# Power_Supply.net
KiCad netlist of a schematic drawn in Altium Designer
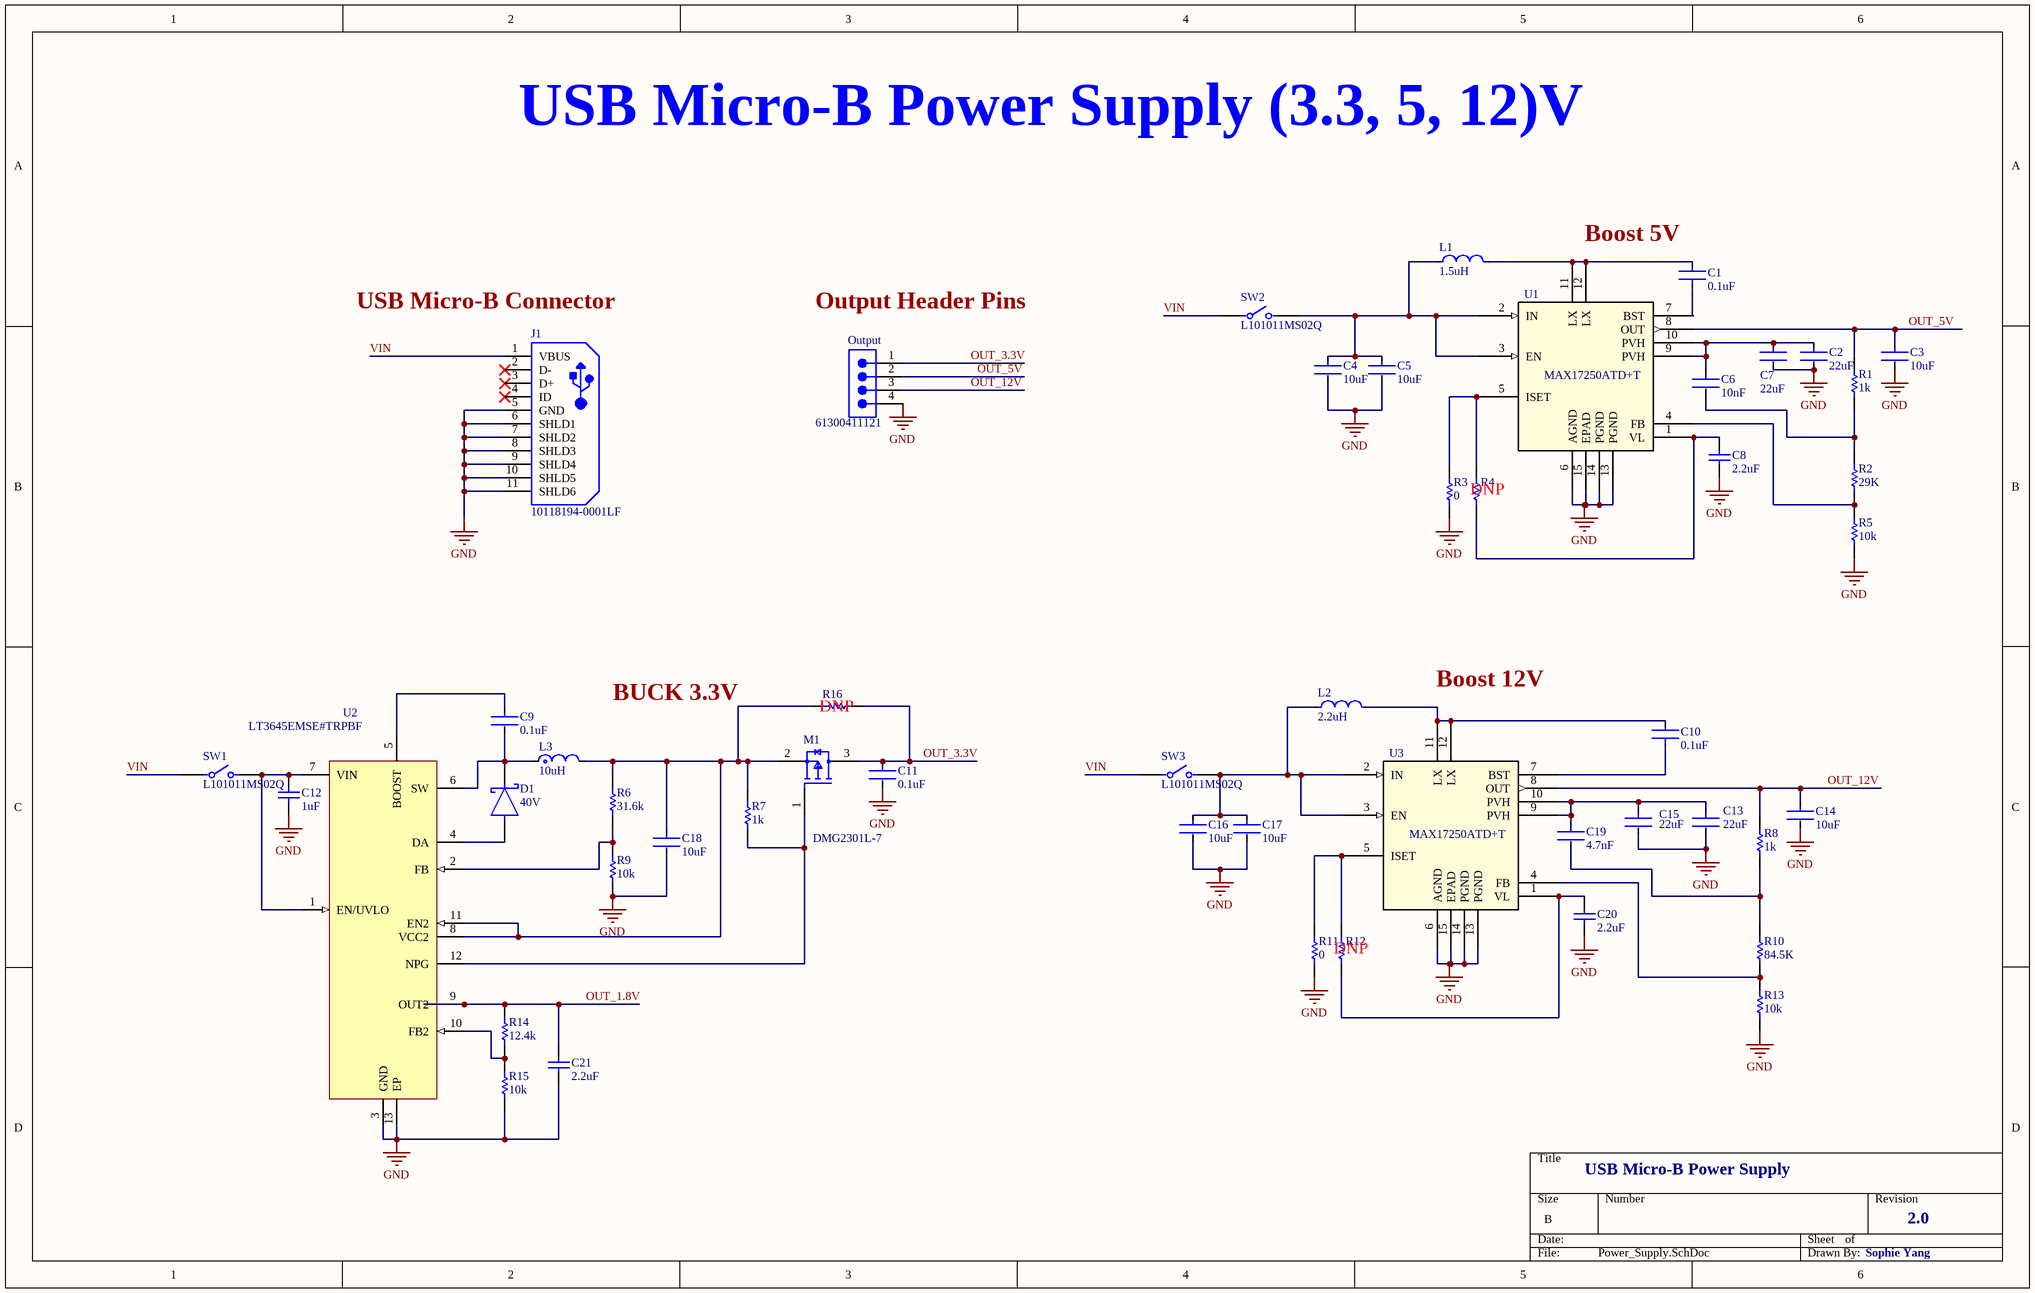
[diagram p0: Power_Supply.SchDoc]

(export (version "E")
  (design (tool "Eeschema 10.0.6"))
  (components
    (comp (ref "C1")
      (value "0.1uF")
      (footprint "CC0805KRX7R9BB104")
      (fields
        (field (name "MANUFACTURER") "Yageo")
        (field (name "MANUFACTURER PART NUMBER") "CC0805KRX7R9BB104")
        (field (name "LCSC PART NUMBER") "C49678")
      )
      (libsource (lib "Schlib") (part "CC0805KRX7R9BB104"))
    )
    (comp (ref "C2")
      (value "22uF")
      (footprint "GRM21BR61C226ME44L")
      (description "CAP CER 22UF 16V X5R 0805")
      (fields
        (field (name "MANUFACTURER") "Murata")
        (field (name "MANUFACTURER PART NUMBER") "GRM21BR61C226ME44L")
      )
      (libsource (lib "Schlib") (part "GRM21BR61C226ME44L"))
    )
    (comp (ref "C3")
      (value "10uF")
      (footprint "GRM21BR61C106KE15K")
      (fields
        (field (name "MANUFACTURER") "Murata")
        (field (name "MANUFACTURER PART NUMBER") "GRM21BR61C106KE15K")
        (field (name "LCSC PART NUMBER") "C408141")
      )
      (libsource (lib "Schlib") (part "GRM21BR61C106KE15K"))
    )
    (comp (ref "C4")
      (value "10uF")
      (footprint "GRM21BR61C106KE15K")
      (fields
        (field (name "MANUFACTURER") "Murata")
        (field (name "MANUFACTURER PART NUMBER") "GRM21BR61C106KE15K")
        (field (name "LCSC PART NUMBER") "C408141")
      )
      (libsource (lib "Schlib") (part "GRM21BR61C106KE15K"))
    )
    (comp (ref "C5")
      (value "10uF")
      (footprint "GRM21BR61C106KE15K")
      (fields
        (field (name "MANUFACTURER") "Murata")
        (field (name "MANUFACTURER PART NUMBER") "GRM21BR61C106KE15K")
        (field (name "LCSC PART NUMBER") "C408141")
      )
      (libsource (lib "Schlib") (part "GRM21BR61C106KE15K"))
    )
    (comp (ref "C6")
      (value "10nF")
      (footprint "C0805C103K5RACTU")
      (fields
        (field (name "MANUFACTURER") "KEMET")
        (field (name "MANUFACTURER PART NUMBER") "C0805C103K5RAC-TU")
      )
      (libsource (lib "Schlib") (part "C0805C103K5RAC-TU"))
    )
    (comp (ref "C7")
      (value "22uF")
      (footprint "GRM21BR61C226ME44L")
      (description "CAP CER 22UF 16V X5R 0805")
      (fields
        (field (name "MANUFACTURER") "Murata")
        (field (name "MANUFACTURER PART NUMBER") "GRM21BR61C226ME44L")
      )
      (libsource (lib "Schlib") (part "GRM21BR61C226ME44L"))
    )
    (comp (ref "C8")
      (value "2.2uF")
      (footprint "C0805C225M8RACTU")
      (description "CAP CER 2.2UF 10V X7R 0805")
      (fields
        (field (name "MANUFACTURER") "KEMET")
        (field (name "MANUFACTURER PART NUMBER") "C0805C225M8RACTU")
      )
      (libsource (lib "Schlib") (part "C0805C225M8RACTU"))
    )
    (comp (ref "C9")
      (value "0.1uF")
      (footprint "CC0805KRX7R9BB104")
      (fields
        (field (name "MANUFACTURER") "Yageo")
        (field (name "MANUFACTURER PART NUMBER") "CC0805KRX7R9BB104")
        (field (name "LCSC PART NUMBER") "C49678")
      )
      (libsource (lib "Schlib") (part "CC0805KRX7R9BB104"))
    )
    (comp (ref "C10")
      (value "0.1uF")
      (footprint "CC0805KRX7R9BB104")
      (fields
        (field (name "MANUFACTURER") "Yageo")
        (field (name "MANUFACTURER PART NUMBER") "CC0805KRX7R9BB104")
        (field (name "LCSC PART NUMBER") "C49678")
      )
      (libsource (lib "Schlib") (part "CC0805KRX7R9BB104"))
    )
    (comp (ref "C11")
      (value "0.1uF")
      (footprint "CC0805KRX7R9BB104")
      (fields
        (field (name "MANUFACTURER") "Yageo")
        (field (name "MANUFACTURER PART NUMBER") "CC0805KRX7R9BB104")
        (field (name "LCSC PART NUMBER") "C49678")
      )
      (libsource (lib "Schlib") (part "CC0805KRX7R9BB104"))
    )
    (comp (ref "C12")
      (value "1uF")
      (footprint "C0805C105K4RACTU")
      (description "CAP CER 1UF 16V X7R 0805")
      (fields
        (field (name "MANUFACTURER") "KEMET")
        (field (name "MANUFACTURER PART NUMBER") "C0805C105K4RACTU")
      )
      (libsource (lib "Schlib") (part "C0805C105K4RACTU"))
    )
    (comp (ref "C13")
      (value "22uF")
      (footprint "GRM32ER71E226KE15L")
      (description "CAP CER 22UF 25V X7R 1210")
      (fields
        (field (name "MANUFACTURER") "Murata")
        (field (name "MANUFACTURER PART NUMBER") "GRM32ER71E226KE15L")
      )
      (libsource (lib "Schlib") (part "GRM32ER71E226KE15L"))
    )
    (comp (ref "C14")
      (value "10uF")
      (footprint "GRM21BZ71E106KE15L")
      (description "CAP CER 10UF 25V X7R 0805")
      (fields
        (field (name "MANUFACTURER") "Murata")
        (field (name "MANUFACTURER PART NUMBER") "GRM21BZ71E106KE15L")
      )
      (libsource (lib "Schlib") (part "GRM21BZ71E106KE15L"))
    )
    (comp (ref "C15")
      (value "22uF")
      (footprint "GRM32ER71E226KE15L")
      (description "CAP CER 22UF 25V X7R 1210")
      (fields
        (field (name "MANUFACTURER") "Murata")
        (field (name "MANUFACTURER PART NUMBER") "GRM32ER71E226KE15L")
      )
      (libsource (lib "Schlib") (part "GRM32ER71E226KE15L"))
    )
    (comp (ref "C16")
      (value "10uF")
      (footprint "GRM21BR61C106KE15K")
      (fields
        (field (name "MANUFACTURER") "Murata")
        (field (name "MANUFACTURER PART NUMBER") "GRM21BR61C106KE15K")
        (field (name "LCSC PART NUMBER") "C408141")
      )
      (libsource (lib "Schlib") (part "GRM21BR61C106KE15K"))
    )
    (comp (ref "C17")
      (value "10uF")
      (footprint "GRM21BR61C106KE15K")
      (fields
        (field (name "MANUFACTURER") "Murata")
        (field (name "MANUFACTURER PART NUMBER") "GRM21BR61C106KE15K")
        (field (name "LCSC PART NUMBER") "C408141")
      )
      (libsource (lib "Schlib") (part "GRM21BR61C106KE15K"))
    )
    (comp (ref "C18")
      (value "10uF")
      (footprint "GRM21BR61C106KE15K")
      (fields
        (field (name "MANUFACTURER") "Murata")
        (field (name "MANUFACTURER PART NUMBER") "GRM21BR61C106KE15K")
        (field (name "LCSC PART NUMBER") "C408141")
      )
      (libsource (lib "Schlib") (part "GRM21BR61C106KE15K"))
    )
    (comp (ref "C19")
      (value "4.7nF")
      (footprint "CC0805KRX7R9BB472")
      (fields
        (field (name "MANUFACTURER") "Yageo")
        (field (name "MANUFACTURER PART NUMBER") "CC0805KRX7R9BB472")
        (field (name "LCSC PART NUMBER") "C107153")
      )
      (libsource (lib "Schlib") (part "CC0805KRX7R9BB472"))
    )
    (comp (ref "C20")
      (value "2.2uF")
      (footprint "C0805C225M8RACTU")
      (description "CAP CER 2.2UF 10V X7R 0805")
      (fields
        (field (name "MANUFACTURER") "KEMET")
        (field (name "MANUFACTURER PART NUMBER") "C0805C225M8RACTU")
      )
      (libsource (lib "Schlib") (part "C0805C225M8RACTU"))
    )
    (comp (ref "C21")
      (value "2.2uF")
      (footprint "C0805C225M8RACTU")
      (description "CAP CER 2.2UF 10V X7R 0805")
      (fields
        (field (name "MANUFACTURER") "KEMET")
        (field (name "MANUFACTURER PART NUMBER") "C0805C225M8RACTU")
      )
      (libsource (lib "Schlib") (part "C0805C225M8RACTU"))
    )
    (comp (ref "D1")
      (value "40V")
      (footprint "B5819WS-TP")
      (description "Rectifier Diode, Schottky, 1 Phase, 1 Element, 1A, 40V V(RRM), Silicon")
      (fields (field (name "MANUFACTURER") "MCC") (field (name "MANUFACTURER PART NUMBER") "B5819WS-TP"))
      (libsource (lib "Schlib") (part "B5819WS-TP"))
    )
    (comp (ref "J1")
      (value "10118194-0001LF")
      (footprint "10118194-0001LF")
      (description "CONN RCPT USB2.0 MICRO B SMD R/A")
      (fields (field (name "MANUFACTURER") "Amphenol ICC / FCI"))
      (libsource (lib "Schlib") (part "10118194-0001LF"))
    )
    (comp (ref "L1")
      (value "1.5uH")
      (footprint "IHLP2020CZER1R5M11")
      (description "FIXED IND 1.5UH 7.5A 18.5MOHM SM")
      (fields
        (field (name "MANUFACTURER") "Vishay Dale")
        (field (name "MANUFACTURER PART NUMBER") "IHLP2020CZER1R5M11")
      )
      (libsource (lib "Schlib") (part "IHLP2020CZER1R5M11"))
    )
    (comp (ref "L2")
      (value "2.2uH")
      (footprint "IHLP2020CZER2R2M11")
      (description "FIXED IND 2.2UH 6.75A 25MOHM SMD")
      (fields
        (field (name "MANUFACTURER") "Vishay Dale")
        (field (name "MANUFACTURER PART NUMBER") "IHLP2020CZER2R2M11")
      )
      (libsource (lib "Schlib") (part "IHLP2020CZER2R2M11"))
    )
    (comp (ref "L3")
      (value "10uH")
      (footprint "VLS6045EX-100M")
      (description "FIXED IND 10UH 3.4A 61 MOHM SMD")
      (fields (field (name "MANUFACTURER") "TDK") (field (name "MANUFACTURER PART NUMBER") "VLS6045EX-100M"))
      (libsource (lib "Schlib") (part "VLS6045EX-100M"))
    )
    (comp (ref "M1")
      (value "DMG2301L-7")
      (footprint "DMG2301L-7")
      (description "MOSFET P-CH 20V 3A SOT23")
      (fields (field (name "MANUFACTURER") "Diodes"))
      (libsource (lib "Schlib") (part "DMG2301L-7"))
    )
    (comp (ref "Output")
      (value "61300411121")
      (footprint "61300411121")
      (description "CONN HEADER VERT 4POS 2.54MM")
      (fields (field (name "MANUFACTURER") "Wurth Electronics"))
      (libsource (lib "Schlib") (part "61300411121"))
    )
    (comp (ref "R1")
      (value "1k")
      (footprint "RC0805FR-071KL")
      (description "RES 1K OHM 1% 1/8W 0805")
      (fields
        (field (name "MANUFACTURER") "Yageo")
        (field (name "MANUFACTURER PART NUMBER") "RC0805FR-071KL")
      )
      (libsource (lib "Schlib") (part "RC0805FR-071KL"))
    )
    (comp (ref "R2")
      (value "29K")
      (footprint "CRCW080528K7FKEA")
      (description "RES SMD 28.7K OHM 1% 1/8W 0805")
      (fields
        (field (name "MANUFACTURER") "Vishay")
        (field (name "MANUFACTURER PART NUMBER") "CRCW080528K7FKEA")
      )
      (libsource (lib "Schlib") (part "CRCW080528K7FKEA"))
    )
    (comp (ref "R3")
      (value "0")
      (footprint "CRCW08050000Z0EA")
      (description "RES SMD 0 OHM JUMPER 1/8W 0805")
      (fields
        (field (name "MANUFACTURER") "Vishay")
        (field (name "MANUFACTURER PART NUMBER") "CRCW08050000Z0EA")
      )
      (libsource (lib "Schlib") (part "CRCW08050000Z0EA"))
    )
    (comp (ref "R4")
      (value "DNP")
      (footprint "CRCW08050000Z0EA")
      (description "RES SMD 0 OHM JUMPER 1/8W 0805")
      (fields
        (field (name "MANUFACTURER") "Vishay")
        (field (name "MANUFACTURER PART NUMBER") "CRCW08050000Z0EA")
      )
      (libsource (lib "Schlib") (part "CRCW08050000Z0EA"))
    )
    (comp (ref "R5")
      (value "10k")
      (footprint "CRCW080510K0FKEA")
      (description "RES SMD 10K OHM 1% 1/8W 0805")
      (fields
        (field (name "MANUFACTURER") "Vishay")
        (field (name "MANUFACTURER PART NUMBER") "CRCW080510K0FKEA")
      )
      (libsource (lib "Schlib") (part "CRCW080510K0FKEA"))
    )
    (comp (ref "R6")
      (value "31.6k")
      (footprint "RC0805FR-0731K6L")
      (description "RES 31.6K OHM 1% 1/8W 0805")
      (fields
        (field (name "MANUFACTURER") "Yageo")
        (field (name "MANUFACTURER PART NUMBER") "RC0805FR-0731K6L")
      )
      (libsource (lib "Schlib") (part "RC0805FR-0731K6L"))
    )
    (comp (ref "R7")
      (value "1k")
      (footprint "RC0805FR-071KL")
      (description "RES 1K OHM 1% 1/8W 0805")
      (fields
        (field (name "MANUFACTURER") "Yageo")
        (field (name "MANUFACTURER PART NUMBER") "RC0805FR-071KL")
      )
      (libsource (lib "Schlib") (part "RC0805FR-071KL"))
    )
    (comp (ref "R8")
      (value "1k")
      (footprint "RC0805FR-071KL")
      (description "RES 1K OHM 1% 1/8W 0805")
      (fields
        (field (name "MANUFACTURER") "Yageo")
        (field (name "MANUFACTURER PART NUMBER") "RC0805FR-071KL")
      )
      (libsource (lib "Schlib") (part "RC0805FR-071KL"))
    )
    (comp (ref "R9")
      (value "10k")
      (footprint "CRCW080510K0FKEA")
      (description "RES SMD 10K OHM 1% 1/8W 0805")
      (fields
        (field (name "MANUFACTURER") "Vishay")
        (field (name "MANUFACTURER PART NUMBER") "CRCW080510K0FKEA")
      )
      (libsource (lib "Schlib") (part "CRCW080510K0FKEA"))
    )
    (comp (ref "R10")
      (value "84.5K")
      (footprint "CRCW080584K5FKEA")
      (description "RES SMD 84.5K OHM 1% 1/8W 0805")
      (fields
        (field (name "MANUFACTURER") "Vishay")
        (field (name "MANUFACTURER PART NUMBER") "CRCW080584K5FKEA")
      )
      (libsource (lib "Schlib") (part "CRCW080584K5FKEA"))
    )
    (comp (ref "R11")
      (value "0")
      (footprint "CRCW08050000Z0EA")
      (description "RES SMD 0 OHM JUMPER 1/8W 0805")
      (fields
        (field (name "MANUFACTURER") "Vishay")
        (field (name "MANUFACTURER PART NUMBER") "CRCW08050000Z0EA")
      )
      (libsource (lib "Schlib") (part "CRCW08050000Z0EA"))
    )
    (comp (ref "R12")
      (value "DNP")
      (footprint "CRCW08050000Z0EA")
      (description "RES SMD 0 OHM JUMPER 1/8W 0805")
      (fields
        (field (name "MANUFACTURER") "Vishay")
        (field (name "MANUFACTURER PART NUMBER") "CRCW08050000Z0EA")
      )
      (libsource (lib "Schlib") (part "CRCW08050000Z0EA"))
    )
    (comp (ref "R13")
      (value "10k")
      (footprint "CRCW080510K0FKEA")
      (description "RES SMD 10K OHM 1% 1/8W 0805")
      (fields
        (field (name "MANUFACTURER") "Vishay")
        (field (name "MANUFACTURER PART NUMBER") "CRCW080510K0FKEA")
      )
      (libsource (lib "Schlib") (part "CRCW080510K0FKEA"))
    )
    (comp (ref "R14")
      (value "12.4k")
      (footprint "CRCW080512K4FKEA")
      (description "RES SMD 12.4K OHM 1% 1/8W 0805")
      (fields
        (field (name "MANUFACTURER") "Vishay")
        (field (name "MANUFACTURER PART NUMBER") "CRCW080512K4FKEA")
      )
      (libsource (lib "Schlib") (part "CRCW080512K4FKEA"))
    )
    (comp (ref "R15")
      (value "10k")
      (footprint "CRCW080510K0FKEA")
      (description "RES SMD 10K OHM 1% 1/8W 0805")
      (fields
        (field (name "MANUFACTURER") "Vishay")
        (field (name "MANUFACTURER PART NUMBER") "CRCW080510K0FKEA")
      )
      (libsource (lib "Schlib") (part "CRCW080510K0FKEA"))
    )
    (comp (ref "R16")
      (value "DNP")
      (footprint "CRCW08050000Z0EA")
      (description "RES SMD 0 OHM JUMPER 1/8W 0805")
      (fields
        (field (name "MANUFACTURER") "Vishay")
        (field (name "MANUFACTURER PART NUMBER") "CRCW08050000Z0EA")
      )
      (libsource (lib "Schlib") (part "CRCW08050000Z0EA"))
    )
    (comp (ref "SW1")
      (value "L101011MS02Q")
      (footprint "FP-L101011MS02Q-MFG")
      (description "SWITCH SLIDE SPST 4A 125V")
      (libsource (lib "Schlib") (part "CMP-10038-000020-1"))
    )
    (comp (ref "SW2")
      (value "L101011MS02Q")
      (footprint "FP-L101011MS02Q-MFG")
      (description "SWITCH SLIDE SPST 4A 125V")
      (libsource (lib "Schlib") (part "CMP-10038-000020-1"))
    )
    (comp (ref "SW3")
      (value "L101011MS02Q")
      (footprint "FP-L101011MS02Q-MFG")
      (description "SWITCH SLIDE SPST 4A 125V")
      (libsource (lib "Schlib") (part "CMP-10038-000020-1"))
    )
    (comp (ref "U1")
      (value "MAX17250ATD+T")
      (footprint "MAX17250ATD+T")
      (description "IC REG BOOST ADJ 14TDFN")
      (fields (field (name "MANUFACTURER") "Maxim") (field (name "LCSC PART NUMBER") "C2072526"))
      (libsource (lib "Schlib") (part "MAX17250ATD+T"))
    )
    (comp (ref "U2")
      (value "LT3645EMSE#TRPBF")
      (footprint "LT3645EMSE#TRPBF")
      (description "IC REG DL BUCK/LNR 750KHZ 12MSOP")
      (fields (field (name "MANUFACTURER") "Analog Devices / Linear Technology"))
      (libsource (lib "Schlib") (part "LT3645EMSE#TRPBF"))
    )
    (comp (ref "U3")
      (value "MAX17250ATD+T")
      (footprint "MAX17250ATD+T")
      (description "IC REG BOOST ADJ 14TDFN")
      (fields (field (name "MANUFACTURER") "Maxim") (field (name "LCSC PART NUMBER") "C2072526"))
      (libsource (lib "Schlib") (part "MAX17250ATD+T"))
    )
  )
  (nets
    (net (code "1") (name "/OUT_1.8V") (class "Default")
      (node (ref "C21") (pin "2") (pinfunction "2_2") (pintype "passive"))
      (node (ref "R14") (pin "2") (pinfunction "2_2") (pintype "passive"))
      (node (ref "U2") (pin "9") (pinfunction "OUT2_9") (pintype "power_in"))
    )
    (net (code "2") (name "/OUT_3.3V") (class "Default")
      (node (ref "C11") (pin "1") (pinfunction "1_1") (pintype "passive"))
      (node (ref "M1") (pin "3") (pinfunction "D_3") (pintype "passive"))
      (node (ref "Output") (pin "1") (pinfunction "1_1") (pintype "passive"))
      (node (ref "R16") (pin "2") (pinfunction "2_2") (pintype "passive"))
    )
    (net (code "3") (name "/OUT_5V") (class "Default")
      (node (ref "C3") (pin "1") (pinfunction "1_1") (pintype "passive"))
      (node (ref "Output") (pin "2") (pinfunction "2_2") (pintype "passive"))
      (node (ref "R1") (pin "2") (pinfunction "2_2") (pintype "passive"))
      (node (ref "U1") (pin "8") (pinfunction "OUT_8") (pintype "output"))
    )
    (net (code "4") (name "/OUT_12V") (class "Default")
      (node (ref "C14") (pin "1") (pinfunction "1_1") (pintype "passive"))
      (node (ref "Output") (pin "3") (pinfunction "3_3") (pintype "passive"))
      (node (ref "R8") (pin "2") (pinfunction "2_2") (pintype "passive"))
      (node (ref "U3") (pin "8") (pinfunction "OUT_8") (pintype "output"))
    )
    (net (code "5") (name "/VIN") (class "Default")
      (node (ref "J1") (pin "1") (pinfunction "VBUS_1") (pintype "passive"))
      (node (ref "SW1") (pin "1") (pinfunction "1_1") (pintype "passive"))
      (node (ref "SW2") (pin "1") (pinfunction "1_1") (pintype "passive"))
      (node (ref "SW3") (pin "1") (pinfunction "1_1") (pintype "passive"))
    )
    (net (code "6") (name "GND") (class "Default")
      (node (ref "C11") (pin "2") (pinfunction "2_2") (pintype "passive"))
      (node (ref "C12") (pin "2") (pinfunction "2_2") (pintype "passive"))
      (node (ref "C13") (pin "2") (pinfunction "2_2") (pintype "passive"))
      (node (ref "C14") (pin "2") (pinfunction "2_2") (pintype "passive"))
      (node (ref "C15") (pin "2") (pinfunction "2_2") (pintype "passive"))
      (node (ref "C16") (pin "2") (pinfunction "2_2") (pintype "passive"))
      (node (ref "C17") (pin "2") (pinfunction "2_2") (pintype "passive"))
      (node (ref "C18") (pin "2") (pinfunction "2_2") (pintype "passive"))
      (node (ref "C2") (pin "2") (pinfunction "2_2") (pintype "passive"))
      (node (ref "C20") (pin "2") (pinfunction "2_2") (pintype "passive"))
      (node (ref "C21") (pin "1") (pinfunction "1_1") (pintype "passive"))
      (node (ref "C3") (pin "2") (pinfunction "2_2") (pintype "passive"))
      (node (ref "C4") (pin "2") (pinfunction "2_2") (pintype "passive"))
      (node (ref "C5") (pin "2") (pinfunction "2_2") (pintype "passive"))
      (node (ref "C7") (pin "2") (pinfunction "2_2") (pintype "passive"))
      (node (ref "C8") (pin "2") (pinfunction "2_2") (pintype "passive"))
      (node (ref "J1") (pin "10") (pinfunction "SHLD5_10") (pintype "passive"))
      (node (ref "J1") (pin "11") (pinfunction "SHLD6_11") (pintype "passive"))
      (node (ref "J1") (pin "5") (pinfunction "GND_5") (pintype "passive"))
      (node (ref "J1") (pin "6") (pinfunction "SHLD1_6") (pintype "passive"))
      (node (ref "J1") (pin "7") (pinfunction "SHLD2_7") (pintype "passive"))
      (node (ref "J1") (pin "8") (pinfunction "SHLD3_8") (pintype "passive"))
      (node (ref "J1") (pin "9") (pinfunction "SHLD4_9") (pintype "passive"))
      (node (ref "Output") (pin "4") (pinfunction "4_4") (pintype "passive"))
      (node (ref "R11") (pin "2") (pinfunction "2_2") (pintype "passive"))
      (node (ref "R13") (pin "1") (pinfunction "1_1") (pintype "passive"))
      (node (ref "R15") (pin "1") (pinfunction "1_1") (pintype "passive"))
      (node (ref "R3") (pin "2") (pinfunction "2_2") (pintype "passive"))
      (node (ref "R5") (pin "1") (pinfunction "1_1") (pintype "passive"))
      (node (ref "R9") (pin "1") (pinfunction "1_1") (pintype "passive"))
      (node (ref "U1") (pin "13") (pinfunction "PGND_13") (pintype "power_in"))
      (node (ref "U1") (pin "14") (pinfunction "PGND_14") (pintype "power_in"))
      (node (ref "U1") (pin "15") (pinfunction "EPAD_15") (pintype "power_in"))
      (node (ref "U1") (pin "6") (pinfunction "AGND_6") (pintype "power_in"))
      (node (ref "U2") (pin "13") (pinfunction "EP_13") (pintype "power_in"))
      (node (ref "U2") (pin "3") (pinfunction "GND_3") (pintype "power_in"))
      (node (ref "U3") (pin "13") (pinfunction "PGND_13") (pintype "power_in"))
      (node (ref "U3") (pin "14") (pinfunction "PGND_14") (pintype "power_in"))
      (node (ref "U3") (pin "15") (pinfunction "EPAD_15") (pintype "power_in"))
      (node (ref "U3") (pin "6") (pinfunction "AGND_6") (pintype "power_in"))
    )
    (net (code "7") (name "Net-(C1-Pad2)") (class "Default")
      (node (ref "C1") (pin "2") (pinfunction "2_2") (pintype "passive"))
      (node (ref "L1") (pin "2") (pinfunction "2_2") (pintype "passive"))
      (node (ref "U1") (pin "11") (pinfunction "LX_11") (pintype "passive"))
      (node (ref "U1") (pin "12") (pinfunction "LX_12") (pintype "passive"))
    )
    (net (code "8") (name "Net-(C2-Pad1)") (class "Default")
      (node (ref "C2") (pin "1") (pinfunction "1_1") (pintype "passive"))
      (node (ref "C6") (pin "1") (pinfunction "1_1") (pintype "passive"))
      (node (ref "C7") (pin "1") (pinfunction "1_1") (pintype "passive"))
      (node (ref "U1") (pin "10") (pinfunction "PVH_10") (pintype "passive"))
      (node (ref "U1") (pin "9") (pinfunction "PVH_9") (pintype "passive"))
    )
    (net (code "9") (name "Net-(C6-Pad2)") (class "Default")
      (node (ref "C6") (pin "2") (pinfunction "2_2") (pintype "passive"))
      (node (ref "R1") (pin "1") (pinfunction "1_1") (pintype "passive"))
      (node (ref "R2") (pin "2") (pinfunction "2_2") (pintype "passive"))
    )
    (net (code "10") (name "Net-(C10-Pad2)") (class "Default")
      (node (ref "C10") (pin "2") (pinfunction "2_2") (pintype "passive"))
      (node (ref "L2") (pin "2") (pinfunction "2_2") (pintype "passive"))
      (node (ref "U3") (pin "11") (pinfunction "LX_11") (pintype "passive"))
      (node (ref "U3") (pin "12") (pinfunction "LX_12") (pintype "passive"))
    )
    (net (code "11") (name "Net-(C13-Pad1)") (class "Default")
      (node (ref "C13") (pin "1") (pinfunction "1_1") (pintype "passive"))
      (node (ref "C15") (pin "1") (pinfunction "1_1") (pintype "passive"))
      (node (ref "C19") (pin "1") (pinfunction "1_1") (pintype "passive"))
      (node (ref "U3") (pin "10") (pinfunction "PVH_10") (pintype "passive"))
      (node (ref "U3") (pin "9") (pinfunction "PVH_9") (pintype "passive"))
    )
    (net (code "12") (name "Net-(C19-Pad2)") (class "Default")
      (node (ref "C19") (pin "2") (pinfunction "2_2") (pintype "passive"))
      (node (ref "R10") (pin "2") (pinfunction "2_2") (pintype "passive"))
      (node (ref "R8") (pin "1") (pinfunction "1_1") (pintype "passive"))
    )
    (net (code "13") (name "Net-(D1-A)") (class "Default")
      (node (ref "D1") (pin "2") (pinfunction "A_2") (pintype "passive"))
      (node (ref "U2") (pin "4") (pinfunction "DA_4") (pintype "passive"))
    )
    (net (code "14") (name "Net-(D1-C)") (class "Default")
      (node (ref "C9") (pin "2") (pinfunction "2_2") (pintype "passive"))
      (node (ref "D1") (pin "1") (pinfunction "C_1") (pintype "passive"))
      (node (ref "L3") (pin "1") (pinfunction "1_1") (pintype "passive"))
      (node (ref "U2") (pin "6") (pinfunction "SW_6") (pintype "power_in"))
    )
    (net (code "15") (name "Net-(M1-G)") (class "Default")
      (node (ref "M1") (pin "1") (pinfunction "G_1") (pintype "passive"))
      (node (ref "R7") (pin "1") (pinfunction "1_1") (pintype "passive"))
      (node (ref "U2") (pin "12") (pinfunction "NPG_12") (pintype "tri_state"))
    )
    (net (code "16") (name "Net-(M1-S)") (class "Default")
      (node (ref "C18") (pin "1") (pinfunction "1_1") (pintype "passive"))
      (node (ref "L3") (pin "2") (pinfunction "2_2") (pintype "passive"))
      (node (ref "M1") (pin "2") (pinfunction "S_2") (pintype "passive"))
      (node (ref "R16") (pin "1") (pinfunction "1_1") (pintype "passive"))
      (node (ref "R6") (pin "2") (pinfunction "2_2") (pintype "passive"))
      (node (ref "R7") (pin "2") (pinfunction "2_2") (pintype "passive"))
      (node (ref "U2") (pin "11") (pinfunction "EN2_11") (pintype "input"))
      (node (ref "U2") (pin "8") (pinfunction "_VCC2_8") (pintype "power_in"))
    )
    (net (code "17") (name "Net-(U1-BST)") (class "Default")
      (node (ref "C1") (pin "1") (pinfunction "1_1") (pintype "passive"))
      (node (ref "U1") (pin "7") (pinfunction "BST_7") (pintype "passive"))
    )
    (net (code "18") (name "Net-(U1-EN)") (class "Default")
      (node (ref "C4") (pin "1") (pinfunction "1_1") (pintype "passive"))
      (node (ref "C5") (pin "1") (pinfunction "1_1") (pintype "passive"))
      (node (ref "L1") (pin "1") (pinfunction "1_1") (pintype "passive"))
      (node (ref "SW2") (pin "2") (pinfunction "2_2") (pintype "passive"))
      (node (ref "U1") (pin "2") (pinfunction "IN_2") (pintype "input"))
      (node (ref "U1") (pin "3") (pinfunction "EN_3") (pintype "input"))
    )
    (net (code "19") (name "Net-(U1-FB)") (class "Default")
      (node (ref "R2") (pin "1") (pinfunction "1_1") (pintype "passive"))
      (node (ref "R5") (pin "2") (pinfunction "2_2") (pintype "passive"))
      (node (ref "U1") (pin "4") (pinfunction "FB_4") (pintype "passive"))
    )
    (net (code "20") (name "Net-(U1-ISET)") (class "Default")
      (node (ref "R3") (pin "1") (pinfunction "1_1") (pintype "passive"))
      (node (ref "R4") (pin "1") (pinfunction "1_1") (pintype "passive"))
      (node (ref "U1") (pin "5") (pinfunction "ISET_5") (pintype "passive"))
    )
    (net (code "21") (name "Net-(U1-VL)") (class "Default")
      (node (ref "C8") (pin "1") (pinfunction "1_1") (pintype "passive"))
      (node (ref "R4") (pin "2") (pinfunction "2_2") (pintype "passive"))
      (node (ref "U1") (pin "1") (pinfunction "VL_1") (pintype "passive"))
    )
    (net (code "22") (name "Net-(U2-BOOST)") (class "Default")
      (node (ref "C9") (pin "1") (pinfunction "1_1") (pintype "passive"))
      (node (ref "U2") (pin "5") (pinfunction "BOOST_5") (pintype "passive"))
    )
    (net (code "23") (name "Net-(U2-EN{slash}UVLO)") (class "Default")
      (node (ref "C12") (pin "1") (pinfunction "1_1") (pintype "passive"))
      (node (ref "SW1") (pin "2") (pinfunction "2_2") (pintype "passive"))
      (node (ref "U2") (pin "1") (pinfunction "EN/UVLO_1") (pintype "input"))
      (node (ref "U2") (pin "7") (pinfunction "VIN_7") (pintype "power_in"))
    )
    (net (code "24") (name "Net-(U2-FB)") (class "Default")
      (node (ref "R6") (pin "1") (pinfunction "1_1") (pintype "passive"))
      (node (ref "R9") (pin "2") (pinfunction "2_2") (pintype "passive"))
      (node (ref "U2") (pin "2") (pinfunction "FB_2") (pintype "input"))
    )
    (net (code "25") (name "Net-(U2-FB2)") (class "Default")
      (node (ref "R14") (pin "1") (pinfunction "1_1") (pintype "passive"))
      (node (ref "R15") (pin "2") (pinfunction "2_2") (pintype "passive"))
      (node (ref "U2") (pin "10") (pinfunction "FB2_10") (pintype "input"))
    )
    (net (code "26") (name "Net-(U3-BST)") (class "Default")
      (node (ref "C10") (pin "1") (pinfunction "1_1") (pintype "passive"))
      (node (ref "U3") (pin "7") (pinfunction "BST_7") (pintype "passive"))
    )
    (net (code "27") (name "Net-(U3-EN)") (class "Default")
      (node (ref "C16") (pin "1") (pinfunction "1_1") (pintype "passive"))
      (node (ref "C17") (pin "1") (pinfunction "1_1") (pintype "passive"))
      (node (ref "L2") (pin "1") (pinfunction "1_1") (pintype "passive"))
      (node (ref "SW3") (pin "2") (pinfunction "2_2") (pintype "passive"))
      (node (ref "U3") (pin "2") (pinfunction "IN_2") (pintype "input"))
      (node (ref "U3") (pin "3") (pinfunction "EN_3") (pintype "input"))
    )
    (net (code "28") (name "Net-(U3-FB)") (class "Default")
      (node (ref "R10") (pin "1") (pinfunction "1_1") (pintype "passive"))
      (node (ref "R13") (pin "2") (pinfunction "2_2") (pintype "passive"))
      (node (ref "U3") (pin "4") (pinfunction "FB_4") (pintype "passive"))
    )
    (net (code "29") (name "Net-(U3-ISET)") (class "Default")
      (node (ref "R11") (pin "1") (pinfunction "1_1") (pintype "passive"))
      (node (ref "R12") (pin "1") (pinfunction "1_1") (pintype "passive"))
      (node (ref "U3") (pin "5") (pinfunction "ISET_5") (pintype "passive"))
    )
    (net (code "30") (name "Net-(U3-VL)") (class "Default")
      (node (ref "C20") (pin "1") (pinfunction "1_1") (pintype "passive"))
      (node (ref "R12") (pin "2") (pinfunction "2_2") (pintype "passive"))
      (node (ref "U3") (pin "1") (pinfunction "VL_1") (pintype "passive"))
    )
    (net (code "31") (name "unconnected-(J1-D+-Pad3)") (class "Default")
      (node (ref "J1") (pin "3") (pinfunction "D+_3") (pintype "passive+no_connect"))
    )
    (net (code "32") (name "unconnected-(J1-D--Pad2)") (class "Default")
      (node (ref "J1") (pin "2") (pinfunction "D-_2") (pintype "passive+no_connect"))
    )
    (net (code "33") (name "unconnected-(J1-ID-Pad4)") (class "Default")
      (node (ref "J1") (pin "4") (pinfunction "ID_4") (pintype "passive+no_connect"))
    )
  )
)
